# AMC_Connector.net
KiCad netlist of a schematic drawn in Altium Designer
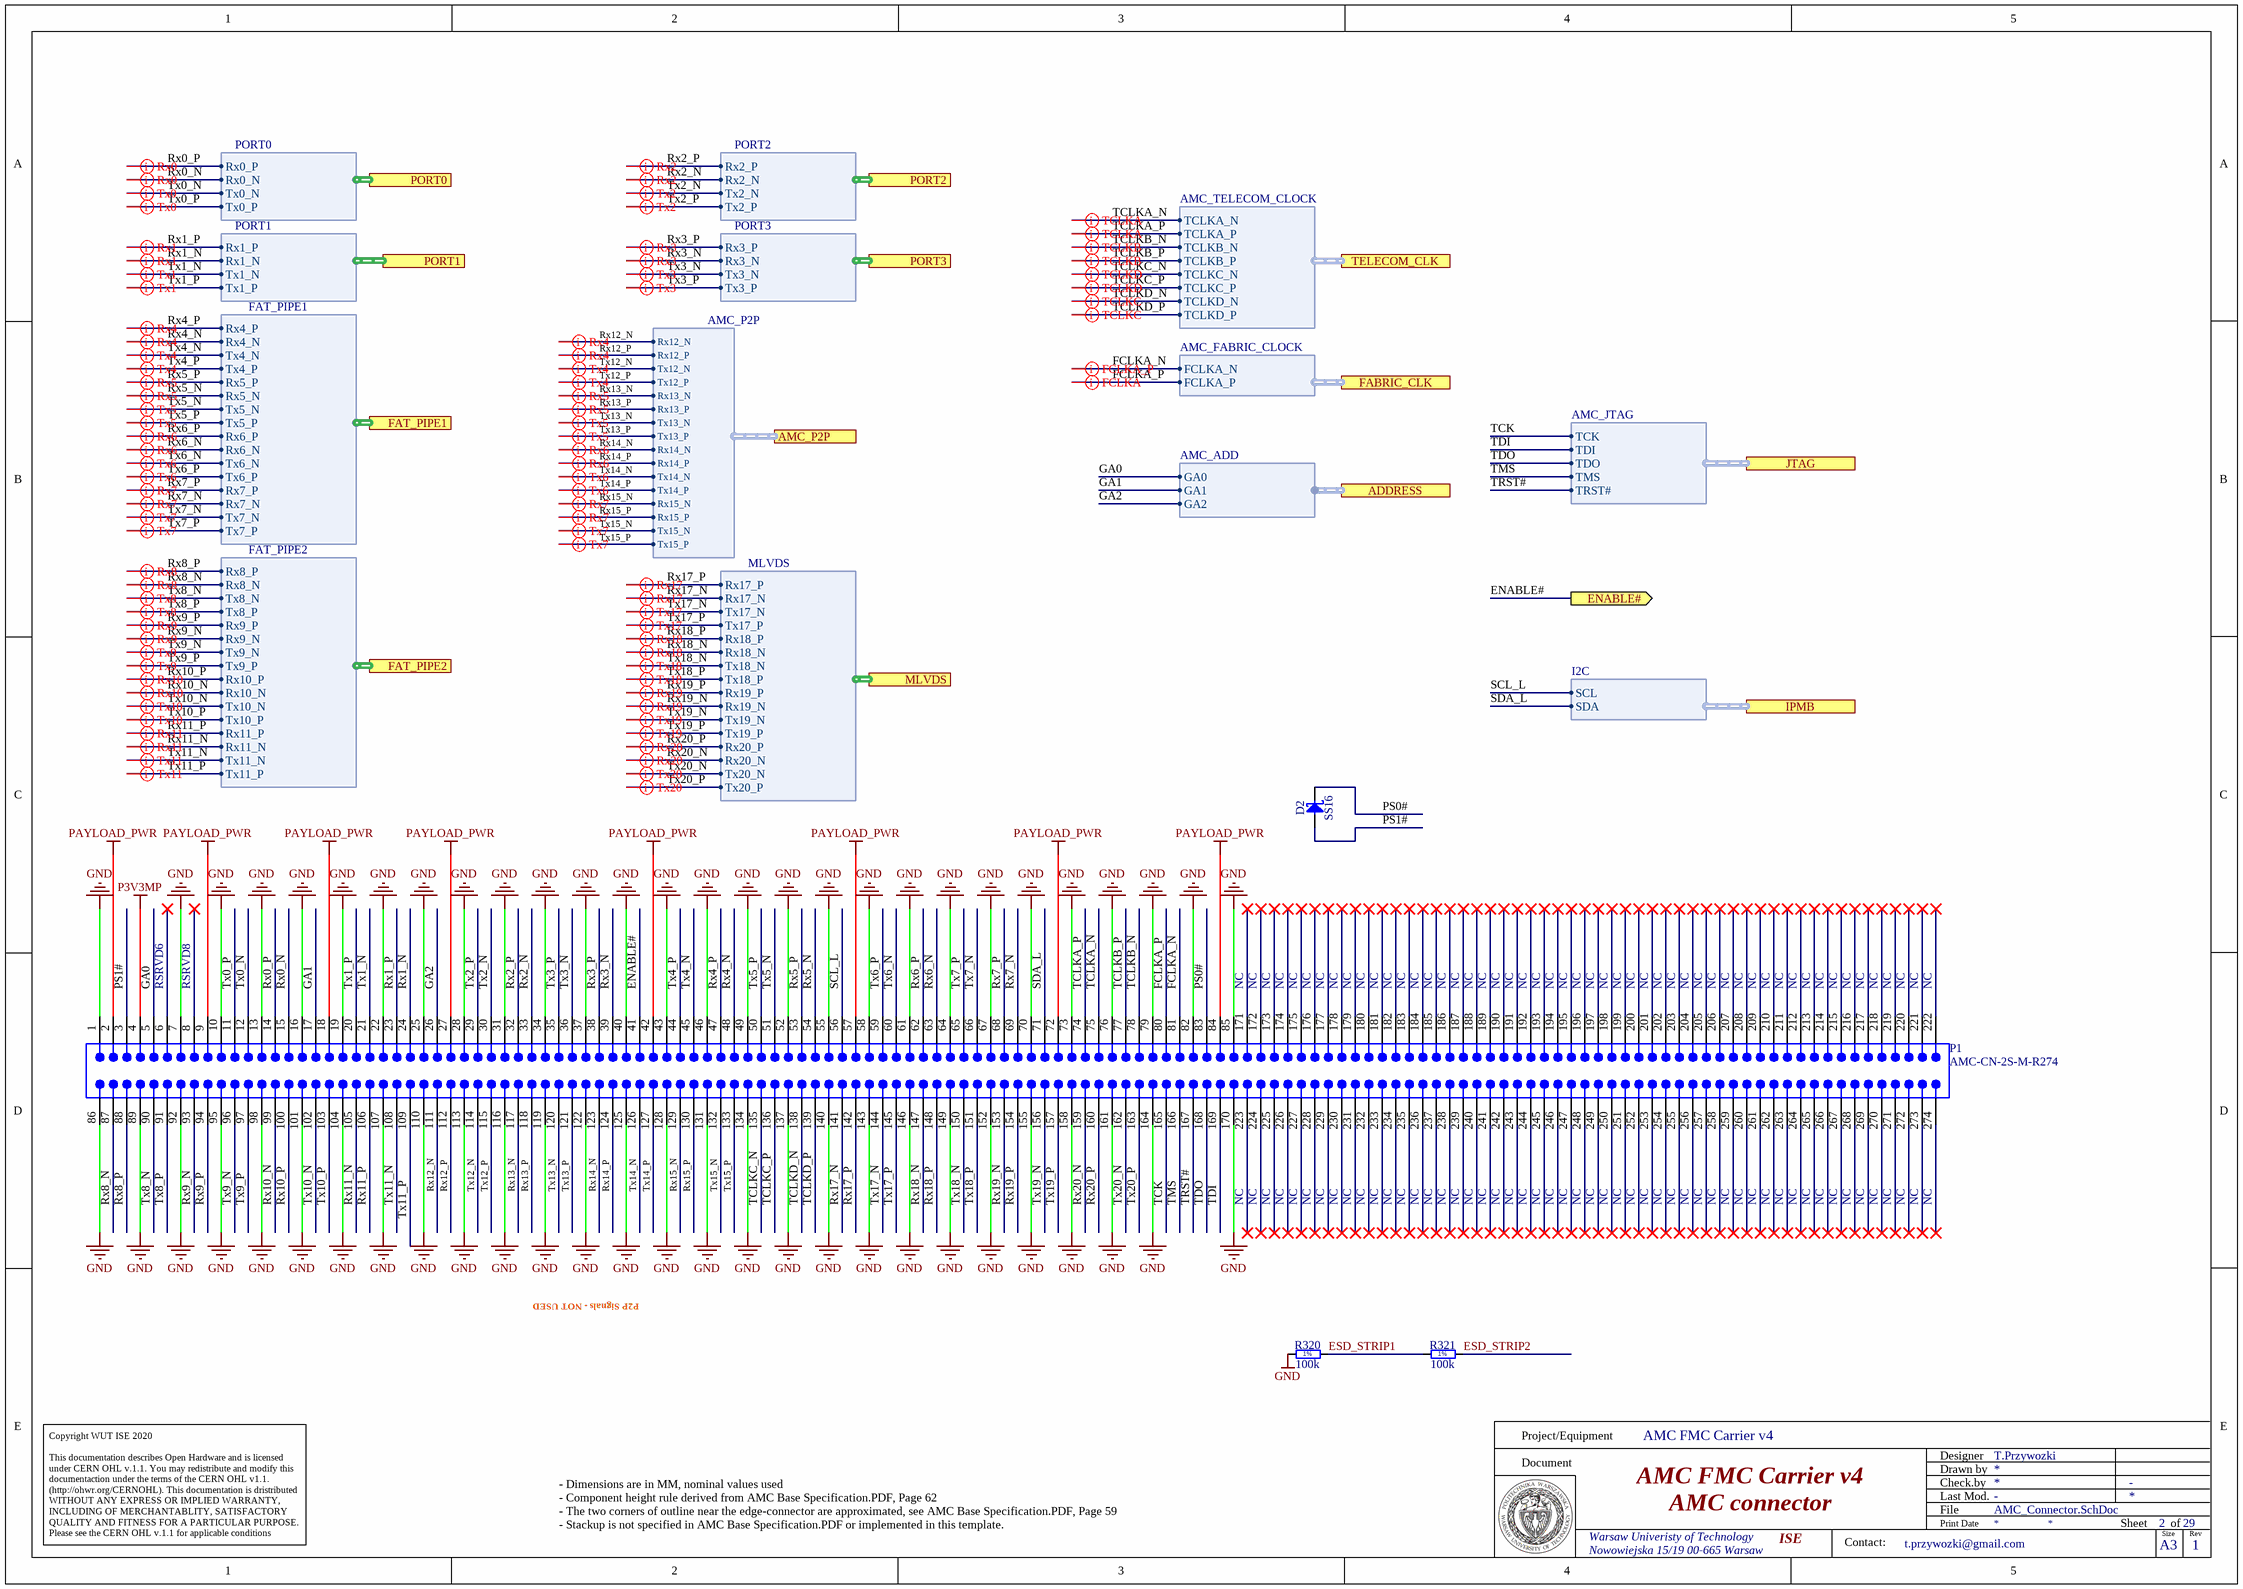
[diagram p0: AMC_Connector.SchDoc]

(export (version "E")
  (design (tool "Eeschema 10.0.6"))
  (components
    (comp (ref "D2")
      (value "SS16")
      (footprint "DIOM5127X229N")
      (description "Schottky Diode")
      (fields
        (field (name "VOLTAGE") "60V")
        (field (name "POWER") "1A")
        (field (name "AUTHOR") "CERN DEM JLC")
      )
      (libsource (lib "ICs And Semiconductors") (part "Diode Schottky"))
    )
    (comp (ref "P1")
      (value "AMC-CN-2S-M-R274")
      (footprint "AMC-GF-2D-750-O274")
      (description "Golden finger, AMC, Dual, Opposite, Pitch 0.75mm, 170-Position")
      (fields (field (name "PUBLISHER") "Altium"))
      (libsource (lib "Altium Shanghai") (part "CMP-0001-00058-2"))
    )
    (comp (ref "R320")
      (value "100k")
      (footprint "RESC3216X65N")
      (description "Resistor - 1%")
      (fields
        (field (name "PART NUMBER") "R1206_100K_1%_0.25W_100PPM")
        (field (name "POWER") "0.25W")
        (field (name "AUTHOR") "CERN DEM JLC")
      )
      (libsource (lib "Resistors") (part "Resistor - 1%"))
    )
    (comp (ref "R321")
      (value "100k")
      (footprint "RESC3216X65N")
      (description "Resistor - 1%")
      (fields
        (field (name "PART NUMBER") "R1206_100K_1%_0.25W_100PPM")
        (field (name "POWER") "0.25W")
        (field (name "AUTHOR") "CERN DEM JLC")
      )
      (libsource (lib "Resistors") (part "Resistor - 1%"))
    )
  )
  (nets
    (net (code "14") (name "/ENABLE#") (class "Default")
      (node (ref "P1") (pin "41") (pinfunction "41_41") (pintype "passive"))
    )
    (net (code "15") (name "/ESD_STRIP1") (class "Default")
      (node (ref "R320") (pin "2") (pinfunction "2_2") (pintype "passive"))
      (node (ref "R321") (pin "1") (pinfunction "1_1") (pintype "passive"))
    )
    (net (code "16") (name "/ESD_STRIP2") (class "Default")
      (node (ref "R321") (pin "2") (pinfunction "2_2") (pintype "passive"))
    )
    (net (code "17") (name "/FCLKA_N") (class "Default")
      (node (ref "P1") (pin "81") (pinfunction "81_81") (pintype "passive"))
    )
    (net (code "18") (name "/FCLKA_P") (class "Default")
      (node (ref "P1") (pin "80") (pinfunction "80_80") (pintype "passive"))
    )
    (net (code "19") (name "/GA0") (class "Default")
      (node (ref "P1") (pin "5") (pinfunction "5_5") (pintype "passive"))
    )
    (net (code "20") (name "/GA1") (class "Default")
      (node (ref "P1") (pin "17") (pinfunction "17_17") (pintype "passive"))
    )
    (net (code "21") (name "/GA2") (class "Default")
      (node (ref "P1") (pin "26") (pinfunction "26_26") (pintype "passive"))
    )
    (net (code "22") (name "/PS0#") (class "Default")
      (node (ref "D2") (pin "1") (pinfunction "C_1") (pintype "passive"))
      (node (ref "P1") (pin "83") (pinfunction "83_83") (pintype "passive"))
    )
    (net (code "23") (name "/PS1#") (class "Default")
      (node (ref "D2") (pin "2") (pinfunction "A_2") (pintype "passive"))
      (node (ref "P1") (pin "3") (pinfunction "3_3") (pintype "passive"))
    )
    (net (code "24") (name "/Rx0_N") (class "Default")
      (node (ref "P1") (pin "15") (pinfunction "15_15") (pintype "passive"))
    )
    (net (code "25") (name "/Rx0_P") (class "Default")
      (node (ref "P1") (pin "14") (pinfunction "14_14") (pintype "passive"))
    )
    (net (code "26") (name "/Rx1_N") (class "Default")
      (node (ref "P1") (pin "24") (pinfunction "24_24") (pintype "passive"))
    )
    (net (code "27") (name "/Rx1_P") (class "Default")
      (node (ref "P1") (pin "23") (pinfunction "23_23") (pintype "passive"))
    )
    (net (code "28") (name "/Rx2_N") (class "Default")
      (node (ref "P1") (pin "33") (pinfunction "33_33") (pintype "passive"))
    )
    (net (code "29") (name "/Rx2_P") (class "Default")
      (node (ref "P1") (pin "32") (pinfunction "32_32") (pintype "passive"))
    )
    (net (code "30") (name "/Rx3_N") (class "Default")
      (node (ref "P1") (pin "39") (pinfunction "39_39") (pintype "passive"))
    )
    (net (code "31") (name "/Rx3_P") (class "Default")
      (node (ref "P1") (pin "38") (pinfunction "38_38") (pintype "passive"))
    )
    (net (code "32") (name "/Rx4_N") (class "Default")
      (node (ref "P1") (pin "48") (pinfunction "48_48") (pintype "passive"))
    )
    (net (code "33") (name "/Rx4_P") (class "Default")
      (node (ref "P1") (pin "47") (pinfunction "47_47") (pintype "passive"))
    )
    (net (code "34") (name "/Rx5_N") (class "Default")
      (node (ref "P1") (pin "54") (pinfunction "54_54") (pintype "passive"))
    )
    (net (code "35") (name "/Rx5_P") (class "Default")
      (node (ref "P1") (pin "53") (pinfunction "53_53") (pintype "passive"))
    )
    (net (code "36") (name "/Rx6_N") (class "Default")
      (node (ref "P1") (pin "63") (pinfunction "63_63") (pintype "passive"))
    )
    (net (code "37") (name "/Rx6_P") (class "Default")
      (node (ref "P1") (pin "62") (pinfunction "62_62") (pintype "passive"))
    )
    (net (code "38") (name "/Rx7_N") (class "Default")
      (node (ref "P1") (pin "69") (pinfunction "69_69") (pintype "passive"))
    )
    (net (code "39") (name "/Rx7_P") (class "Default")
      (node (ref "P1") (pin "68") (pinfunction "68_68") (pintype "passive"))
    )
    (net (code "40") (name "/Rx8_N") (class "Default")
      (node (ref "P1") (pin "87") (pinfunction "87_87") (pintype "passive"))
    )
    (net (code "41") (name "/Rx8_P") (class "Default")
      (node (ref "P1") (pin "88") (pinfunction "88_88") (pintype "passive"))
    )
    (net (code "42") (name "/Rx9_N") (class "Default")
      (node (ref "P1") (pin "93") (pinfunction "93_93") (pintype "passive"))
    )
    (net (code "43") (name "/Rx9_P") (class "Default")
      (node (ref "P1") (pin "94") (pinfunction "94_94") (pintype "passive"))
    )
    (net (code "44") (name "/Rx10_N") (class "Default")
      (node (ref "P1") (pin "99") (pinfunction "99_99") (pintype "passive"))
    )
    (net (code "45") (name "/Rx10_P") (class "Default")
      (node (ref "P1") (pin "100") (pinfunction "100_100") (pintype "passive"))
    )
    (net (code "46") (name "/Rx11_N") (class "Default")
      (node (ref "P1") (pin "105") (pinfunction "105_105") (pintype "passive"))
    )
    (net (code "47") (name "/Rx11_P") (class "Default")
      (node (ref "P1") (pin "106") (pinfunction "106_106") (pintype "passive"))
    )
    (net (code "48") (name "/Rx12_N") (class "Default")
      (node (ref "P1") (pin "111") (pinfunction "111_111") (pintype "passive"))
    )
    (net (code "49") (name "/Rx12_P") (class "Default")
      (node (ref "P1") (pin "112") (pinfunction "112_112") (pintype "passive"))
    )
    (net (code "50") (name "/Rx13_N") (class "Default")
      (node (ref "P1") (pin "117") (pinfunction "117_117") (pintype "passive"))
    )
    (net (code "51") (name "/Rx13_P") (class "Default")
      (node (ref "P1") (pin "118") (pinfunction "118_118") (pintype "passive"))
    )
    (net (code "52") (name "/Rx14_N") (class "Default")
      (node (ref "P1") (pin "123") (pinfunction "123_123") (pintype "passive"))
    )
    (net (code "53") (name "/Rx14_P") (class "Default")
      (node (ref "P1") (pin "124") (pinfunction "124_124") (pintype "passive"))
    )
    (net (code "54") (name "/Rx15_N") (class "Default")
      (node (ref "P1") (pin "129") (pinfunction "129_129") (pintype "passive"))
    )
    (net (code "55") (name "/Rx15_P") (class "Default")
      (node (ref "P1") (pin "130") (pinfunction "130_130") (pintype "passive"))
    )
    (net (code "56") (name "/Rx17_N") (class "Default")
      (node (ref "P1") (pin "141") (pinfunction "141_141") (pintype "passive"))
    )
    (net (code "57") (name "/Rx17_P") (class "Default")
      (node (ref "P1") (pin "142") (pinfunction "142_142") (pintype "passive"))
    )
    (net (code "58") (name "/Rx18_N") (class "Default")
      (node (ref "P1") (pin "147") (pinfunction "147_147") (pintype "passive"))
    )
    (net (code "59") (name "/Rx18_P") (class "Default")
      (node (ref "P1") (pin "148") (pinfunction "148_148") (pintype "passive"))
    )
    (net (code "60") (name "/Rx19_N") (class "Default")
      (node (ref "P1") (pin "153") (pinfunction "153_153") (pintype "passive"))
    )
    (net (code "61") (name "/Rx19_P") (class "Default")
      (node (ref "P1") (pin "154") (pinfunction "154_154") (pintype "passive"))
    )
    (net (code "62") (name "/Rx20_N") (class "Default")
      (node (ref "P1") (pin "159") (pinfunction "159_159") (pintype "passive"))
    )
    (net (code "63") (name "/Rx20_P") (class "Default")
      (node (ref "P1") (pin "160") (pinfunction "160_160") (pintype "passive"))
    )
    (net (code "64") (name "/SCL_L") (class "Default")
      (node (ref "P1") (pin "56") (pinfunction "56_56") (pintype "passive"))
    )
    (net (code "65") (name "/SDA_L") (class "Default")
      (node (ref "P1") (pin "71") (pinfunction "71_71") (pintype "passive"))
    )
    (net (code "66") (name "/TCK") (class "Default")
      (node (ref "P1") (pin "165") (pinfunction "165_165") (pintype "passive"))
    )
    (net (code "67") (name "/TCLKA_N") (class "Default")
      (node (ref "P1") (pin "75") (pinfunction "75_75") (pintype "passive"))
    )
    (net (code "68") (name "/TCLKA_P") (class "Default")
      (node (ref "P1") (pin "74") (pinfunction "74_74") (pintype "passive"))
    )
    (net (code "69") (name "/TCLKB_N") (class "Default")
      (node (ref "P1") (pin "78") (pinfunction "78_78") (pintype "passive"))
    )
    (net (code "70") (name "/TCLKB_P") (class "Default")
      (node (ref "P1") (pin "77") (pinfunction "77_77") (pintype "passive"))
    )
    (net (code "71") (name "/TCLKC_N") (class "Default")
      (node (ref "P1") (pin "135") (pinfunction "135_135") (pintype "passive"))
    )
    (net (code "72") (name "/TCLKC_P") (class "Default")
      (node (ref "P1") (pin "136") (pinfunction "136_136") (pintype "passive"))
    )
    (net (code "73") (name "/TCLKD_N") (class "Default")
      (node (ref "P1") (pin "138") (pinfunction "138_138") (pintype "passive"))
    )
    (net (code "74") (name "/TCLKD_P") (class "Default")
      (node (ref "P1") (pin "139") (pinfunction "139_139") (pintype "passive"))
    )
    (net (code "75") (name "/TDI") (class "Default")
      (node (ref "P1") (pin "169") (pinfunction "169_169") (pintype "passive"))
    )
    (net (code "76") (name "/TDO") (class "Default")
      (node (ref "P1") (pin "168") (pinfunction "168_168") (pintype "passive"))
    )
    (net (code "77") (name "/TMS") (class "Default")
      (node (ref "P1") (pin "166") (pinfunction "166_166") (pintype "passive"))
    )
    (net (code "78") (name "/TRST#") (class "Default")
      (node (ref "P1") (pin "167") (pinfunction "167_167") (pintype "passive"))
    )
    (net (code "79") (name "/Tx0_N") (class "Default")
      (node (ref "P1") (pin "12") (pinfunction "12_12") (pintype "passive"))
    )
    (net (code "80") (name "/Tx0_P") (class "Default")
      (node (ref "P1") (pin "11") (pinfunction "11_11") (pintype "passive"))
    )
    (net (code "81") (name "/Tx1_N") (class "Default")
      (node (ref "P1") (pin "21") (pinfunction "21_21") (pintype "passive"))
    )
    (net (code "82") (name "/Tx1_P") (class "Default")
      (node (ref "P1") (pin "20") (pinfunction "20_20") (pintype "passive"))
    )
    (net (code "83") (name "/Tx2_N") (class "Default")
      (node (ref "P1") (pin "30") (pinfunction "30_30") (pintype "passive"))
    )
    (net (code "84") (name "/Tx2_P") (class "Default")
      (node (ref "P1") (pin "29") (pinfunction "29_29") (pintype "passive"))
    )
    (net (code "85") (name "/Tx3_N") (class "Default")
      (node (ref "P1") (pin "36") (pinfunction "36_36") (pintype "passive"))
    )
    (net (code "86") (name "/Tx3_P") (class "Default")
      (node (ref "P1") (pin "35") (pinfunction "35_35") (pintype "passive"))
    )
    (net (code "87") (name "/Tx4_N") (class "Default")
      (node (ref "P1") (pin "45") (pinfunction "45_45") (pintype "passive"))
    )
    (net (code "88") (name "/Tx4_P") (class "Default")
      (node (ref "P1") (pin "44") (pinfunction "44_44") (pintype "passive"))
    )
    (net (code "89") (name "/Tx5_N") (class "Default")
      (node (ref "P1") (pin "51") (pinfunction "51_51") (pintype "passive"))
    )
    (net (code "90") (name "/Tx5_P") (class "Default")
      (node (ref "P1") (pin "50") (pinfunction "50_50") (pintype "passive"))
    )
    (net (code "91") (name "/Tx6_N") (class "Default")
      (node (ref "P1") (pin "60") (pinfunction "60_60") (pintype "passive"))
    )
    (net (code "92") (name "/Tx6_P") (class "Default")
      (node (ref "P1") (pin "59") (pinfunction "59_59") (pintype "passive"))
    )
    (net (code "93") (name "/Tx7_N") (class "Default")
      (node (ref "P1") (pin "66") (pinfunction "66_66") (pintype "passive"))
    )
    (net (code "94") (name "/Tx7_P") (class "Default")
      (node (ref "P1") (pin "65") (pinfunction "65_65") (pintype "passive"))
    )
    (net (code "95") (name "/Tx8_N") (class "Default")
      (node (ref "P1") (pin "90") (pinfunction "90_90") (pintype "passive"))
    )
    (net (code "96") (name "/Tx8_P") (class "Default")
      (node (ref "P1") (pin "91") (pinfunction "91_91") (pintype "passive"))
    )
    (net (code "97") (name "/Tx9_N") (class "Default")
      (node (ref "P1") (pin "96") (pinfunction "96_96") (pintype "passive"))
    )
    (net (code "98") (name "/Tx9_P") (class "Default")
      (node (ref "P1") (pin "97") (pinfunction "97_97") (pintype "passive"))
    )
    (net (code "99") (name "/Tx10_N") (class "Default")
      (node (ref "P1") (pin "102") (pinfunction "102_102") (pintype "passive"))
    )
    (net (code "100") (name "/Tx10_P") (class "Default")
      (node (ref "P1") (pin "103") (pinfunction "103_103") (pintype "passive"))
    )
    (net (code "101") (name "/Tx11_N") (class "Default")
      (node (ref "P1") (pin "108") (pinfunction "108_108") (pintype "passive"))
    )
    (net (code "102") (name "/Tx11_P") (class "Default")
      (node (ref "P1") (pin "109") (pinfunction "109_109") (pintype "passive"))
    )
    (net (code "103") (name "/Tx12_N") (class "Default")
      (node (ref "P1") (pin "114") (pinfunction "114_114") (pintype "passive"))
    )
    (net (code "104") (name "/Tx12_P") (class "Default")
      (node (ref "P1") (pin "115") (pinfunction "115_115") (pintype "passive"))
    )
    (net (code "105") (name "/Tx13_N") (class "Default")
      (node (ref "P1") (pin "120") (pinfunction "120_120") (pintype "passive"))
    )
    (net (code "106") (name "/Tx13_P") (class "Default")
      (node (ref "P1") (pin "121") (pinfunction "121_121") (pintype "passive"))
    )
    (net (code "107") (name "/Tx14_N") (class "Default")
      (node (ref "P1") (pin "126") (pinfunction "126_126") (pintype "passive"))
    )
    (net (code "108") (name "/Tx14_P") (class "Default")
      (node (ref "P1") (pin "127") (pinfunction "127_127") (pintype "passive"))
    )
    (net (code "109") (name "/Tx15_N") (class "Default")
      (node (ref "P1") (pin "132") (pinfunction "132_132") (pintype "passive"))
    )
    (net (code "110") (name "/Tx15_P") (class "Default")
      (node (ref "P1") (pin "133") (pinfunction "133_133") (pintype "passive"))
    )
    (net (code "111") (name "/Tx17_N") (class "Default")
      (node (ref "P1") (pin "144") (pinfunction "144_144") (pintype "passive"))
    )
    (net (code "112") (name "/Tx17_P") (class "Default")
      (node (ref "P1") (pin "145") (pinfunction "145_145") (pintype "passive"))
    )
    (net (code "113") (name "/Tx18_N") (class "Default")
      (node (ref "P1") (pin "150") (pinfunction "150_150") (pintype "passive"))
    )
    (net (code "114") (name "/Tx18_P") (class "Default")
      (node (ref "P1") (pin "151") (pinfunction "151_151") (pintype "passive"))
    )
    (net (code "115") (name "/Tx19_N") (class "Default")
      (node (ref "P1") (pin "156") (pinfunction "156_156") (pintype "passive"))
    )
    (net (code "116") (name "/Tx19_P") (class "Default")
      (node (ref "P1") (pin "157") (pinfunction "157_157") (pintype "passive"))
    )
    (net (code "117") (name "/Tx20_N") (class "Default")
      (node (ref "P1") (pin "162") (pinfunction "162_162") (pintype "passive"))
    )
    (net (code "118") (name "/Tx20_P") (class "Default")
      (node (ref "P1") (pin "163") (pinfunction "163_163") (pintype "passive"))
    )
    (net (code "132") (name "GND") (class "Default")
      (node (ref "P1") (pin "1") (pinfunction "1_1") (pintype "passive"))
      (node (ref "P1") (pin "10") (pinfunction "10_10") (pintype "passive"))
      (node (ref "P1") (pin "101") (pinfunction "101_101") (pintype "passive"))
      (node (ref "P1") (pin "104") (pinfunction "104_104") (pintype "passive"))
      (node (ref "P1") (pin "107") (pinfunction "107_107") (pintype "passive"))
      (node (ref "P1") (pin "110") (pinfunction "110_110") (pintype "passive"))
      (node (ref "P1") (pin "113") (pinfunction "113_113") (pintype "passive"))
      (node (ref "P1") (pin "116") (pinfunction "116_116") (pintype "passive"))
      (node (ref "P1") (pin "119") (pinfunction "119_119") (pintype "passive"))
      (node (ref "P1") (pin "122") (pinfunction "122_122") (pintype "passive"))
      (node (ref "P1") (pin "125") (pinfunction "125_125") (pintype "passive"))
      (node (ref "P1") (pin "128") (pinfunction "128_128") (pintype "passive"))
      (node (ref "P1") (pin "13") (pinfunction "13_13") (pintype "passive"))
      (node (ref "P1") (pin "131") (pinfunction "131_131") (pintype "passive"))
      (node (ref "P1") (pin "134") (pinfunction "134_134") (pintype "passive"))
      (node (ref "P1") (pin "137") (pinfunction "137_137") (pintype "passive"))
      (node (ref "P1") (pin "140") (pinfunction "140_140") (pintype "passive"))
      (node (ref "P1") (pin "143") (pinfunction "143_143") (pintype "passive"))
      (node (ref "P1") (pin "146") (pinfunction "146_146") (pintype "passive"))
      (node (ref "P1") (pin "149") (pinfunction "149_149") (pintype "passive"))
      (node (ref "P1") (pin "152") (pinfunction "152_152") (pintype "passive"))
      (node (ref "P1") (pin "155") (pinfunction "155_155") (pintype "passive"))
      (node (ref "P1") (pin "158") (pinfunction "158_158") (pintype "passive"))
      (node (ref "P1") (pin "16") (pinfunction "16_16") (pintype "passive"))
      (node (ref "P1") (pin "161") (pinfunction "161_161") (pintype "passive"))
      (node (ref "P1") (pin "164") (pinfunction "164_164") (pintype "passive"))
      (node (ref "P1") (pin "170") (pinfunction "170_170") (pintype "passive"))
      (node (ref "P1") (pin "19") (pinfunction "19_19") (pintype "passive"))
      (node (ref "P1") (pin "22") (pinfunction "22_22") (pintype "passive"))
      (node (ref "P1") (pin "25") (pinfunction "25_25") (pintype "passive"))
      (node (ref "P1") (pin "28") (pinfunction "28_28") (pintype "passive"))
      (node (ref "P1") (pin "31") (pinfunction "31_31") (pintype "passive"))
      (node (ref "P1") (pin "34") (pinfunction "34_34") (pintype "passive"))
      (node (ref "P1") (pin "37") (pinfunction "37_37") (pintype "passive"))
      (node (ref "P1") (pin "40") (pinfunction "40_40") (pintype "passive"))
      (node (ref "P1") (pin "43") (pinfunction "43_43") (pintype "passive"))
      (node (ref "P1") (pin "46") (pinfunction "46_46") (pintype "passive"))
      (node (ref "P1") (pin "49") (pinfunction "49_49") (pintype "passive"))
      (node (ref "P1") (pin "52") (pinfunction "52_52") (pintype "passive"))
      (node (ref "P1") (pin "55") (pinfunction "55_55") (pintype "passive"))
      (node (ref "P1") (pin "58") (pinfunction "58_58") (pintype "passive"))
      (node (ref "P1") (pin "61") (pinfunction "61_61") (pintype "passive"))
      (node (ref "P1") (pin "64") (pinfunction "64_64") (pintype "passive"))
      (node (ref "P1") (pin "67") (pinfunction "67_67") (pintype "passive"))
      (node (ref "P1") (pin "7") (pinfunction "7_7") (pintype "passive"))
      (node (ref "P1") (pin "70") (pinfunction "70_70") (pintype "passive"))
      (node (ref "P1") (pin "73") (pinfunction "73_73") (pintype "passive"))
      (node (ref "P1") (pin "76") (pinfunction "76_76") (pintype "passive"))
      (node (ref "P1") (pin "79") (pinfunction "79_79") (pintype "passive"))
      (node (ref "P1") (pin "82") (pinfunction "82_82") (pintype "passive"))
      (node (ref "P1") (pin "85") (pinfunction "85_85") (pintype "passive"))
      (node (ref "P1") (pin "86") (pinfunction "86_86") (pintype "passive"))
      (node (ref "P1") (pin "89") (pinfunction "89_89") (pintype "passive"))
      (node (ref "P1") (pin "92") (pinfunction "92_92") (pintype "passive"))
      (node (ref "P1") (pin "95") (pinfunction "95_95") (pintype "passive"))
      (node (ref "P1") (pin "98") (pinfunction "98_98") (pintype "passive"))
      (node (ref "R320") (pin "1") (pinfunction "1_1") (pintype "passive"))
    )
    (net (code "133") (name "P3V3MP") (class "Default")
      (node (ref "P1") (pin "4") (pinfunction "4_4") (pintype "passive"))
    )
    (net (code "134") (name "PAYLOAD_PWR") (class "Default")
      (node (ref "P1") (pin "18") (pinfunction "18_18") (pintype "passive"))
      (node (ref "P1") (pin "2") (pinfunction "2_2") (pintype "passive"))
      (node (ref "P1") (pin "27") (pinfunction "27_27") (pintype "passive"))
      (node (ref "P1") (pin "42") (pinfunction "42_42") (pintype "passive"))
      (node (ref "P1") (pin "57") (pinfunction "57_57") (pintype "passive"))
      (node (ref "P1") (pin "72") (pinfunction "72_72") (pintype "passive"))
      (node (ref "P1") (pin "84") (pinfunction "84_84") (pintype "passive"))
      (node (ref "P1") (pin "9") (pinfunction "9_9") (pintype "passive"))
    )
    (net (code "135") (name "unconnected-(P1-Pad6)") (class "Default")
      (node (ref "P1") (pin "6") (pinfunction "6_6") (pintype "passive+no_connect"))
    )
    (net (code "136") (name "unconnected-(P1-Pad8)") (class "Default")
      (node (ref "P1") (pin "8") (pinfunction "8_8") (pintype "passive+no_connect"))
    )
    (net (code "137") (name "unconnected-(P1-Pad171)") (class "Default")
      (node (ref "P1") (pin "171") (pinfunction "171_171") (pintype "passive+no_connect"))
    )
    (net (code "138") (name "unconnected-(P1-Pad172)") (class "Default")
      (node (ref "P1") (pin "172") (pinfunction "172_172") (pintype "passive+no_connect"))
    )
    (net (code "139") (name "unconnected-(P1-Pad173)") (class "Default")
      (node (ref "P1") (pin "173") (pinfunction "173_173") (pintype "passive+no_connect"))
    )
    (net (code "140") (name "unconnected-(P1-Pad174)") (class "Default")
      (node (ref "P1") (pin "174") (pinfunction "174_174") (pintype "passive+no_connect"))
    )
    (net (code "141") (name "unconnected-(P1-Pad175)") (class "Default")
      (node (ref "P1") (pin "175") (pinfunction "175_175") (pintype "passive+no_connect"))
    )
    (net (code "142") (name "unconnected-(P1-Pad176)") (class "Default")
      (node (ref "P1") (pin "176") (pinfunction "176_176") (pintype "passive+no_connect"))
    )
    (net (code "143") (name "unconnected-(P1-Pad177)") (class "Default")
      (node (ref "P1") (pin "177") (pinfunction "177_177") (pintype "passive+no_connect"))
    )
    (net (code "144") (name "unconnected-(P1-Pad178)") (class "Default")
      (node (ref "P1") (pin "178") (pinfunction "178_178") (pintype "passive+no_connect"))
    )
    (net (code "145") (name "unconnected-(P1-Pad179)") (class "Default")
      (node (ref "P1") (pin "179") (pinfunction "179_179") (pintype "passive+no_connect"))
    )
    (net (code "146") (name "unconnected-(P1-Pad180)") (class "Default")
      (node (ref "P1") (pin "180") (pinfunction "180_180") (pintype "passive+no_connect"))
    )
    (net (code "147") (name "unconnected-(P1-Pad181)") (class "Default")
      (node (ref "P1") (pin "181") (pinfunction "181_181") (pintype "passive+no_connect"))
    )
    (net (code "148") (name "unconnected-(P1-Pad182)") (class "Default")
      (node (ref "P1") (pin "182") (pinfunction "182_182") (pintype "passive+no_connect"))
    )
    (net (code "149") (name "unconnected-(P1-Pad183)") (class "Default")
      (node (ref "P1") (pin "183") (pinfunction "183_183") (pintype "passive+no_connect"))
    )
    (net (code "150") (name "unconnected-(P1-Pad184)") (class "Default")
      (node (ref "P1") (pin "184") (pinfunction "184_184") (pintype "passive+no_connect"))
    )
    (net (code "151") (name "unconnected-(P1-Pad185)") (class "Default")
      (node (ref "P1") (pin "185") (pinfunction "185_185") (pintype "passive+no_connect"))
    )
    (net (code "152") (name "unconnected-(P1-Pad186)") (class "Default")
      (node (ref "P1") (pin "186") (pinfunction "186_186") (pintype "passive+no_connect"))
    )
    (net (code "153") (name "unconnected-(P1-Pad187)") (class "Default")
      (node (ref "P1") (pin "187") (pinfunction "187_187") (pintype "passive+no_connect"))
    )
    (net (code "154") (name "unconnected-(P1-Pad188)") (class "Default")
      (node (ref "P1") (pin "188") (pinfunction "188_188") (pintype "passive+no_connect"))
    )
    (net (code "155") (name "unconnected-(P1-Pad189)") (class "Default")
      (node (ref "P1") (pin "189") (pinfunction "189_189") (pintype "passive+no_connect"))
    )
    (net (code "156") (name "unconnected-(P1-Pad190)") (class "Default")
      (node (ref "P1") (pin "190") (pinfunction "190_190") (pintype "passive+no_connect"))
    )
    (net (code "157") (name "unconnected-(P1-Pad191)") (class "Default")
      (node (ref "P1") (pin "191") (pinfunction "191_191") (pintype "passive+no_connect"))
    )
    (net (code "158") (name "unconnected-(P1-Pad192)") (class "Default")
      (node (ref "P1") (pin "192") (pinfunction "192_192") (pintype "passive+no_connect"))
    )
    (net (code "159") (name "unconnected-(P1-Pad193)") (class "Default")
      (node (ref "P1") (pin "193") (pinfunction "193_193") (pintype "passive+no_connect"))
    )
    (net (code "160") (name "unconnected-(P1-Pad194)") (class "Default")
      (node (ref "P1") (pin "194") (pinfunction "194_194") (pintype "passive+no_connect"))
    )
    (net (code "161") (name "unconnected-(P1-Pad195)") (class "Default")
      (node (ref "P1") (pin "195") (pinfunction "195_195") (pintype "passive+no_connect"))
    )
    (net (code "162") (name "unconnected-(P1-Pad196)") (class "Default")
      (node (ref "P1") (pin "196") (pinfunction "196_196") (pintype "passive+no_connect"))
    )
    (net (code "163") (name "unconnected-(P1-Pad197)") (class "Default")
      (node (ref "P1") (pin "197") (pinfunction "197_197") (pintype "passive+no_connect"))
    )
    (net (code "164") (name "unconnected-(P1-Pad198)") (class "Default")
      (node (ref "P1") (pin "198") (pinfunction "198_198") (pintype "passive+no_connect"))
    )
    (net (code "165") (name "unconnected-(P1-Pad199)") (class "Default")
      (node (ref "P1") (pin "199") (pinfunction "199_199") (pintype "passive+no_connect"))
    )
    (net (code "166") (name "unconnected-(P1-Pad200)") (class "Default")
      (node (ref "P1") (pin "200") (pinfunction "200_200") (pintype "passive+no_connect"))
    )
    (net (code "167") (name "unconnected-(P1-Pad201)") (class "Default")
      (node (ref "P1") (pin "201") (pinfunction "201_201") (pintype "passive+no_connect"))
    )
    (net (code "168") (name "unconnected-(P1-Pad202)") (class "Default")
      (node (ref "P1") (pin "202") (pinfunction "202_202") (pintype "passive+no_connect"))
    )
    (net (code "169") (name "unconnected-(P1-Pad203)") (class "Default")
      (node (ref "P1") (pin "203") (pinfunction "203_203") (pintype "passive+no_connect"))
    )
    (net (code "170") (name "unconnected-(P1-Pad204)") (class "Default")
      (node (ref "P1") (pin "204") (pinfunction "204_204") (pintype "passive+no_connect"))
    )
    (net (code "171") (name "unconnected-(P1-Pad205)") (class "Default")
      (node (ref "P1") (pin "205") (pinfunction "205_205") (pintype "passive+no_connect"))
    )
    (net (code "172") (name "unconnected-(P1-Pad206)") (class "Default")
      (node (ref "P1") (pin "206") (pinfunction "206_206") (pintype "passive+no_connect"))
    )
    (net (code "173") (name "unconnected-(P1-Pad207)") (class "Default")
      (node (ref "P1") (pin "207") (pinfunction "207_207") (pintype "passive+no_connect"))
    )
    (net (code "174") (name "unconnected-(P1-Pad208)") (class "Default")
      (node (ref "P1") (pin "208") (pinfunction "208_208") (pintype "passive+no_connect"))
    )
    (net (code "175") (name "unconnected-(P1-Pad209)") (class "Default")
      (node (ref "P1") (pin "209") (pinfunction "209_209") (pintype "passive+no_connect"))
    )
    (net (code "176") (name "unconnected-(P1-Pad210)") (class "Default")
      (node (ref "P1") (pin "210") (pinfunction "210_210") (pintype "passive+no_connect"))
    )
    (net (code "177") (name "unconnected-(P1-Pad211)") (class "Default")
      (node (ref "P1") (pin "211") (pinfunction "211_211") (pintype "passive+no_connect"))
    )
    (net (code "178") (name "unconnected-(P1-Pad212)") (class "Default")
      (node (ref "P1") (pin "212") (pinfunction "212_212") (pintype "passive+no_connect"))
    )
    (net (code "179") (name "unconnected-(P1-Pad213)") (class "Default")
      (node (ref "P1") (pin "213") (pinfunction "213_213") (pintype "passive+no_connect"))
    )
    (net (code "180") (name "unconnected-(P1-Pad214)") (class "Default")
      (node (ref "P1") (pin "214") (pinfunction "214_214") (pintype "passive+no_connect"))
    )
    (net (code "181") (name "unconnected-(P1-Pad215)") (class "Default")
      (node (ref "P1") (pin "215") (pinfunction "215_215") (pintype "passive+no_connect"))
    )
    (net (code "182") (name "unconnected-(P1-Pad216)") (class "Default")
      (node (ref "P1") (pin "216") (pinfunction "216_216") (pintype "passive+no_connect"))
    )
    (net (code "183") (name "unconnected-(P1-Pad217)") (class "Default")
      (node (ref "P1") (pin "217") (pinfunction "217_217") (pintype "passive+no_connect"))
    )
    (net (code "184") (name "unconnected-(P1-Pad218)") (class "Default")
      (node (ref "P1") (pin "218") (pinfunction "218_218") (pintype "passive+no_connect"))
    )
    (net (code "185") (name "unconnected-(P1-Pad219)") (class "Default")
      (node (ref "P1") (pin "219") (pinfunction "219_219") (pintype "passive+no_connect"))
    )
    (net (code "186") (name "unconnected-(P1-Pad220)") (class "Default")
      (node (ref "P1") (pin "220") (pinfunction "220_220") (pintype "passive+no_connect"))
    )
    (net (code "187") (name "unconnected-(P1-Pad221)") (class "Default")
      (node (ref "P1") (pin "221") (pinfunction "221_221") (pintype "passive+no_connect"))
    )
    (net (code "188") (name "unconnected-(P1-Pad222)") (class "Default")
      (node (ref "P1") (pin "222") (pinfunction "222_222") (pintype "passive+no_connect"))
    )
    (net (code "189") (name "unconnected-(P1-Pad223)") (class "Default")
      (node (ref "P1") (pin "223") (pinfunction "223_223") (pintype "passive+no_connect"))
    )
    (net (code "190") (name "unconnected-(P1-Pad224)") (class "Default")
      (node (ref "P1") (pin "224") (pinfunction "224_224") (pintype "passive+no_connect"))
    )
    (net (code "191") (name "unconnected-(P1-Pad225)") (class "Default")
      (node (ref "P1") (pin "225") (pinfunction "225_225") (pintype "passive+no_connect"))
    )
    (net (code "192") (name "unconnected-(P1-Pad226)") (class "Default")
      (node (ref "P1") (pin "226") (pinfunction "226_226") (pintype "passive+no_connect"))
    )
    (net (code "193") (name "unconnected-(P1-Pad227)") (class "Default")
      (node (ref "P1") (pin "227") (pinfunction "227_227") (pintype "passive+no_connect"))
    )
    (net (code "194") (name "unconnected-(P1-Pad228)") (class "Default")
      (node (ref "P1") (pin "228") (pinfunction "228_228") (pintype "passive+no_connect"))
    )
    (net (code "195") (name "unconnected-(P1-Pad229)") (class "Default")
      (node (ref "P1") (pin "229") (pinfunction "229_229") (pintype "passive+no_connect"))
    )
    (net (code "196") (name "unconnected-(P1-Pad230)") (class "Default")
      (node (ref "P1") (pin "230") (pinfunction "230_230") (pintype "passive+no_connect"))
    )
    (net (code "197") (name "unconnected-(P1-Pad231)") (class "Default")
      (node (ref "P1") (pin "231") (pinfunction "231_231") (pintype "passive+no_connect"))
    )
    (net (code "198") (name "unconnected-(P1-Pad232)") (class "Default")
      (node (ref "P1") (pin "232") (pinfunction "232_232") (pintype "passive+no_connect"))
    )
    (net (code "199") (name "unconnected-(P1-Pad233)") (class "Default")
      (node (ref "P1") (pin "233") (pinfunction "233_233") (pintype "passive+no_connect"))
    )
    (net (code "200") (name "unconnected-(P1-Pad234)") (class "Default")
      (node (ref "P1") (pin "234") (pinfunction "234_234") (pintype "passive+no_connect"))
    )
    (net (code "201") (name "unconnected-(P1-Pad235)") (class "Default")
      (node (ref "P1") (pin "235") (pinfunction "235_235") (pintype "passive+no_connect"))
    )
    (net (code "202") (name "unconnected-(P1-Pad236)") (class "Default")
      (node (ref "P1") (pin "236") (pinfunction "236_236") (pintype "passive+no_connect"))
    )
    (net (code "203") (name "unconnected-(P1-Pad237)") (class "Default")
      (node (ref "P1") (pin "237") (pinfunction "237_237") (pintype "passive+no_connect"))
    )
    (net (code "204") (name "unconnected-(P1-Pad238)") (class "Default")
      (node (ref "P1") (pin "238") (pinfunction "238_238") (pintype "passive+no_connect"))
    )
    (net (code "205") (name "unconnected-(P1-Pad239)") (class "Default")
      (node (ref "P1") (pin "239") (pinfunction "239_239") (pintype "passive+no_connect"))
    )
    (net (code "206") (name "unconnected-(P1-Pad240)") (class "Default")
      (node (ref "P1") (pin "240") (pinfunction "240_240") (pintype "passive+no_connect"))
    )
    (net (code "207") (name "unconnected-(P1-Pad241)") (class "Default")
      (node (ref "P1") (pin "241") (pinfunction "241_241") (pintype "passive+no_connect"))
    )
    (net (code "208") (name "unconnected-(P1-Pad242)") (class "Default")
      (node (ref "P1") (pin "242") (pinfunction "242_242") (pintype "passive+no_connect"))
    )
    (net (code "209") (name "unconnected-(P1-Pad243)") (class "Default")
      (node (ref "P1") (pin "243") (pinfunction "243_243") (pintype "passive+no_connect"))
    )
    (net (code "210") (name "unconnected-(P1-Pad244)") (class "Default")
      (node (ref "P1") (pin "244") (pinfunction "244_244") (pintype "passive+no_connect"))
    )
    (net (code "211") (name "unconnected-(P1-Pad245)") (class "Default")
      (node (ref "P1") (pin "245") (pinfunction "245_245") (pintype "passive+no_connect"))
    )
    (net (code "212") (name "unconnected-(P1-Pad246)") (class "Default")
      (node (ref "P1") (pin "246") (pinfunction "246_246") (pintype "passive+no_connect"))
    )
    (net (code "213") (name "unconnected-(P1-Pad247)") (class "Default")
      (node (ref "P1") (pin "247") (pinfunction "247_247") (pintype "passive+no_connect"))
    )
    (net (code "214") (name "unconnected-(P1-Pad248)") (class "Default")
      (node (ref "P1") (pin "248") (pinfunction "248_248") (pintype "passive+no_connect"))
    )
    (net (code "215") (name "unconnected-(P1-Pad249)") (class "Default")
      (node (ref "P1") (pin "249") (pinfunction "249_249") (pintype "passive+no_connect"))
    )
    (net (code "216") (name "unconnected-(P1-Pad250)") (class "Default")
      (node (ref "P1") (pin "250") (pinfunction "250_250") (pintype "passive+no_connect"))
    )
    (net (code "217") (name "unconnected-(P1-Pad251)") (class "Default")
      (node (ref "P1") (pin "251") (pinfunction "251_251") (pintype "passive+no_connect"))
    )
    (net (code "218") (name "unconnected-(P1-Pad252)") (class "Default")
      (node (ref "P1") (pin "252") (pinfunction "252_252") (pintype "passive+no_connect"))
    )
    (net (code "219") (name "unconnected-(P1-Pad253)") (class "Default")
      (node (ref "P1") (pin "253") (pinfunction "253_253") (pintype "passive+no_connect"))
    )
    (net (code "220") (name "unconnected-(P1-Pad254)") (class "Default")
      (node (ref "P1") (pin "254") (pinfunction "254_254") (pintype "passive+no_connect"))
    )
    (net (code "221") (name "unconnected-(P1-Pad255)") (class "Default")
      (node (ref "P1") (pin "255") (pinfunction "255_255") (pintype "passive+no_connect"))
    )
    (net (code "222") (name "unconnected-(P1-Pad256)") (class "Default")
      (node (ref "P1") (pin "256") (pinfunction "256_256") (pintype "passive+no_connect"))
    )
    (net (code "223") (name "unconnected-(P1-Pad257)") (class "Default")
      (node (ref "P1") (pin "257") (pinfunction "257_257") (pintype "passive+no_connect"))
    )
    (net (code "224") (name "unconnected-(P1-Pad258)") (class "Default")
      (node (ref "P1") (pin "258") (pinfunction "258_258") (pintype "passive+no_connect"))
    )
    (net (code "225") (name "unconnected-(P1-Pad259)") (class "Default")
      (node (ref "P1") (pin "259") (pinfunction "259_259") (pintype "passive+no_connect"))
    )
    (net (code "226") (name "unconnected-(P1-Pad260)") (class "Default")
      (node (ref "P1") (pin "260") (pinfunction "260_260") (pintype "passive+no_connect"))
    )
    (net (code "227") (name "unconnected-(P1-Pad261)") (class "Default")
      (node (ref "P1") (pin "261") (pinfunction "261_261") (pintype "passive+no_connect"))
    )
    (net (code "228") (name "unconnected-(P1-Pad262)") (class "Default")
      (node (ref "P1") (pin "262") (pinfunction "262_262") (pintype "passive+no_connect"))
    )
    (net (code "229") (name "unconnected-(P1-Pad263)") (class "Default")
      (node (ref "P1") (pin "263") (pinfunction "263_263") (pintype "passive+no_connect"))
    )
    (net (code "230") (name "unconnected-(P1-Pad264)") (class "Default")
      (node (ref "P1") (pin "264") (pinfunction "264_264") (pintype "passive+no_connect"))
    )
    (net (code "231") (name "unconnected-(P1-Pad265)") (class "Default")
      (node (ref "P1") (pin "265") (pinfunction "265_265") (pintype "passive+no_connect"))
    )
    (net (code "232") (name "unconnected-(P1-Pad266)") (class "Default")
      (node (ref "P1") (pin "266") (pinfunction "266_266") (pintype "passive+no_connect"))
    )
    (net (code "233") (name "unconnected-(P1-Pad267)") (class "Default")
      (node (ref "P1") (pin "267") (pinfunction "267_267") (pintype "passive+no_connect"))
    )
    (net (code "234") (name "unconnected-(P1-Pad268)") (class "Default")
      (node (ref "P1") (pin "268") (pinfunction "268_268") (pintype "passive+no_connect"))
    )
    (net (code "235") (name "unconnected-(P1-Pad269)") (class "Default")
      (node (ref "P1") (pin "269") (pinfunction "269_269") (pintype "passive+no_connect"))
    )
    (net (code "236") (name "unconnected-(P1-Pad270)") (class "Default")
      (node (ref "P1") (pin "270") (pinfunction "270_270") (pintype "passive+no_connect"))
    )
    (net (code "237") (name "unconnected-(P1-Pad271)") (class "Default")
      (node (ref "P1") (pin "271") (pinfunction "271_271") (pintype "passive+no_connect"))
    )
    (net (code "238") (name "unconnected-(P1-Pad272)") (class "Default")
      (node (ref "P1") (pin "272") (pinfunction "272_272") (pintype "passive+no_connect"))
    )
    (net (code "239") (name "unconnected-(P1-Pad273)") (class "Default")
      (node (ref "P1") (pin "273") (pinfunction "273_273") (pintype "passive+no_connect"))
    )
    (net (code "240") (name "unconnected-(P1-Pad274)") (class "Default")
      (node (ref "P1") (pin "274") (pinfunction "274_274") (pintype "passive+no_connect"))
    )
  )
)
